# HabTrackerPiZero_Shield.net
KiCad netlist of a schematic drawn in EAGLE
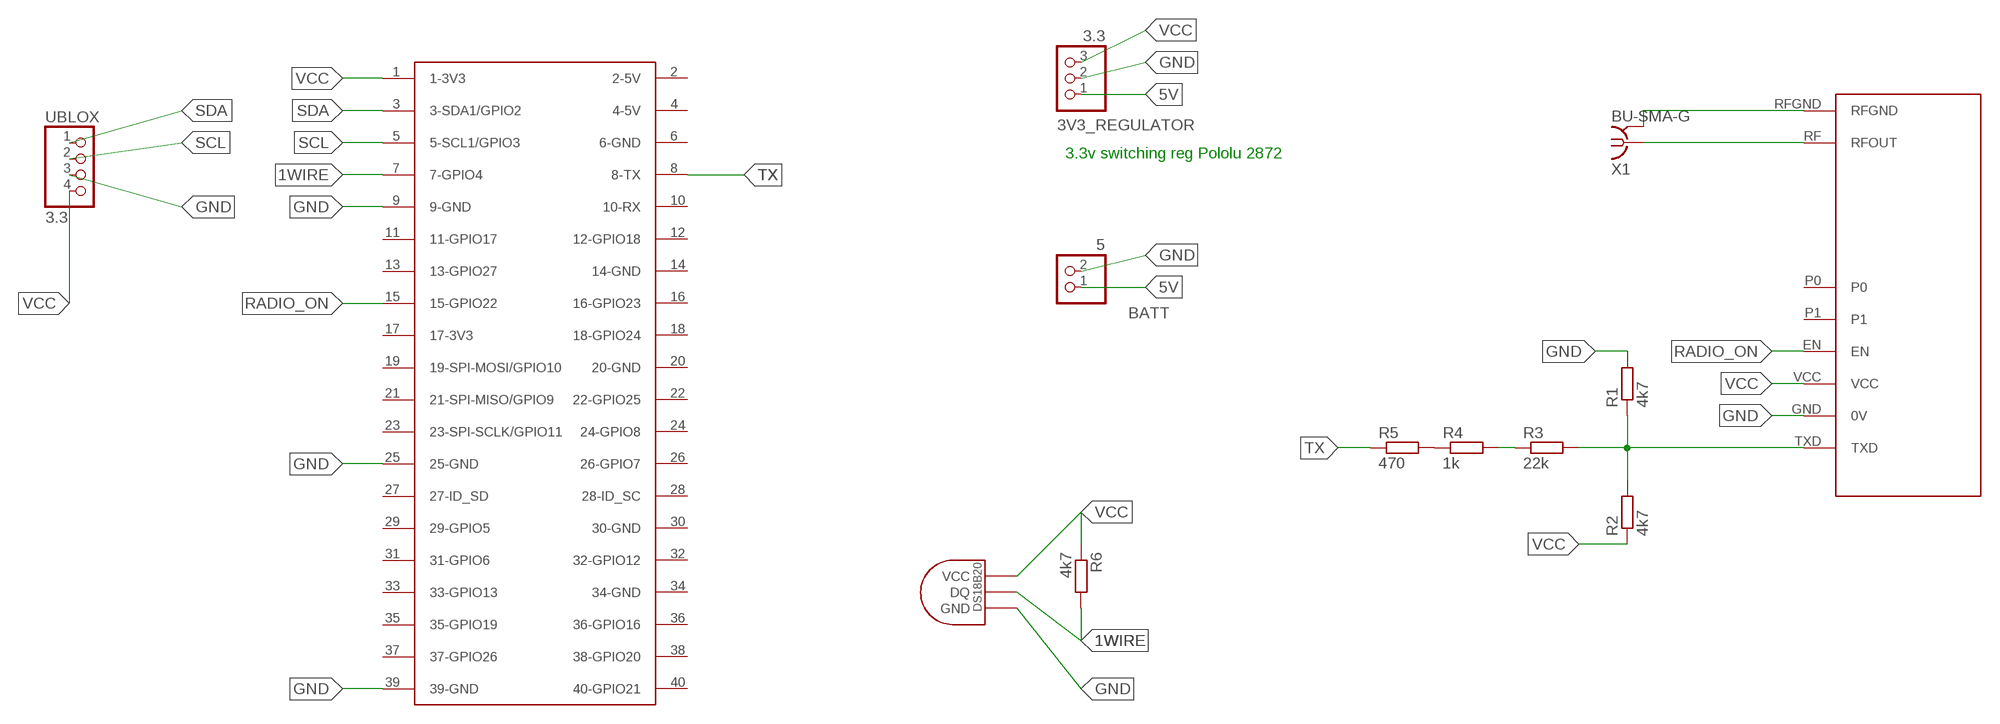
[diagram p0: schematic, sheet 1]

(export (version "E")
  (design (tool "Eeschema 10.0.6"))
  (components
    (comp (ref "3V3_REGULATOR")
      (value "3.3")
      (footprint "eagle-import:1X03")
      (libsource (lib "eagle-import") (part "PINHD-1X3"))
    )
    (comp (ref "BATT")
      (value "5")
      (footprint "eagle-import:1X02")
      (libsource (lib "eagle-import") (part "PINHD-1X2"))
    )
    (comp (ref "R1")
      (value "4k7")
      (footprint "eagle-import:0204_7")
      (libsource (lib "eagle-import") (part "R-EU_0204/7"))
    )
    (comp (ref "R2")
      (value "4k7")
      (footprint "eagle-import:0204_7")
      (libsource (lib "eagle-import") (part "R-EU_0204/7"))
    )
    (comp (ref "R3")
      (value "22k")
      (footprint "eagle-import:0204_7")
      (libsource (lib "eagle-import") (part "R-EU_0204/7"))
    )
    (comp (ref "R4")
      (value "1k")
      (footprint "eagle-import:0204_7")
      (libsource (lib "eagle-import") (part "R-EU_0204/7"))
    )
    (comp (ref "R5")
      (value "470")
      (footprint "eagle-import:0204_7")
      (libsource (lib "eagle-import") (part "R-EU_0204/7"))
    )
    (comp (ref "R6")
      (value "4k7")
      (footprint "eagle-import:0204_7")
      (libsource (lib "eagle-import") (part "R-EU_0204/7"))
    )
    (comp (ref "U$1")
      (value "RASPBERRY-PI+PIZERO")
      (footprint "eagle-import:RASPBERRY-PI-ZERO")
      (libsource (lib "eagle-import") (part "RASPBERRY-PI+PIZERO"))
    )
    (comp (ref "U$2")
      (value "DS1820TO92")
      (footprint "eagle-import:DS1820")
      (libsource (lib "eagle-import") (part "DS1820TO92"))
    )
    (comp (ref "U$3")
      (value "RADIOMETRIX-MTX2")
      (footprint "eagle-import:RADIOMETRIX-MTX2")
      (libsource (lib "eagle-import") (part "RADIOMETRIX-MTX2"))
    )
    (comp (ref "UBLOX")
      (value "3.3")
      (footprint "eagle-import:1X04")
      (libsource (lib "eagle-import") (part "PINHD-1X4"))
    )
    (comp (ref "X1")
      (value "BU-SMA-G")
      (footprint "eagle-import:BU-SMA-G")
      (libsource (lib "eagle-import") (part "BU-SMA-G"))
    )
  )
  (nets
    (net (code "1") (name "1WIRE") (class "Default")
      (node (ref "R6") (pin "2") (pinfunction "2_2") (pintype "passive"))
      (node (ref "U$1") (pin "7") (pinfunction "7-GPIO4_7") (pintype "bidirectional"))
      (node (ref "U$2") (pin "DQ") (pinfunction "DQ_DQ") (pintype "bidirectional"))
    )
    (net (code "2") (name "5V") (class "Default")
      (node (ref "3V3_REGULATOR") (pin "1") (pinfunction "1_1") (pintype "passive"))
      (node (ref "BATT") (pin "1") (pinfunction "1_1") (pintype "passive"))
    )
    (net (code "3") (name "GND") (class "Default")
      (node (ref "3V3_REGULATOR") (pin "2") (pinfunction "2_2") (pintype "passive"))
      (node (ref "BATT") (pin "2") (pinfunction "2_2") (pintype "passive"))
      (node (ref "R1") (pin "2") (pinfunction "2_2") (pintype "passive"))
      (node (ref "U$1") (pin "25") (pinfunction "25-GND_25") (pintype "bidirectional"))
      (node (ref "U$1") (pin "39") (pinfunction "39-GND_39") (pintype "bidirectional"))
      (node (ref "U$1") (pin "9") (pinfunction "9-GND_9") (pintype "bidirectional"))
      (node (ref "U$2") (pin "GND") (pinfunction "GND_GND") (pintype "power_in"))
      (node (ref "U$3") (pin "GND") (pinfunction "0V_GND") (pintype "bidirectional"))
      (node (ref "UBLOX") (pin "3") (pinfunction "3_3") (pintype "passive"))
    )
    (net (code "4") (name "Net-(R1-Pad1)") (class "Default")
      (node (ref "R1") (pin "1") (pinfunction "1_1") (pintype "passive"))
      (node (ref "R2") (pin "2") (pinfunction "2_2") (pintype "passive"))
      (node (ref "R3") (pin "2") (pinfunction "2_2") (pintype "passive"))
      (node (ref "U$3") (pin "TXD") (pinfunction "TXD_TXD") (pintype "bidirectional"))
    )
    (net (code "5") (name "Net-(R3-Pad1)") (class "Default")
      (node (ref "R3") (pin "1") (pinfunction "1_1") (pintype "passive"))
      (node (ref "R4") (pin "2") (pinfunction "2_2") (pintype "passive"))
    )
    (net (code "6") (name "Net-(R4-Pad1)") (class "Default")
      (node (ref "R4") (pin "1") (pinfunction "1_1") (pintype "passive"))
      (node (ref "R5") (pin "2") (pinfunction "2_2") (pintype "passive"))
    )
    (net (code "7") (name "Net-(U$3-PadRFGND)") (class "Default")
      (node (ref "U$3") (pin "RFGND") (pinfunction "RFGND_RFGND") (pintype "bidirectional"))
      (node (ref "X1") (pin "2") (pinfunction "2_2") (pintype "passive"))
      (node (ref "X1") (pin "3") (pinfunction "2_3") (pintype "passive"))
      (node (ref "X1") (pin "4") (pinfunction "2_4") (pintype "passive"))
      (node (ref "X1") (pin "5") (pinfunction "2_5") (pintype "passive"))
    )
    (net (code "8") (name "Net-(U$3-RFOUT)") (class "Default")
      (node (ref "U$3") (pin "RF") (pinfunction "RFOUT_RF") (pintype "bidirectional"))
      (node (ref "X1") (pin "1") (pinfunction "1_1") (pintype "passive"))
    )
    (net (code "9") (name "RADIO_ON") (class "Default")
      (node (ref "U$1") (pin "15") (pinfunction "15-GPIO22_15") (pintype "bidirectional"))
      (node (ref "U$3") (pin "EN") (pinfunction "EN_EN") (pintype "bidirectional"))
    )
    (net (code "10") (name "SCL") (class "Default")
      (node (ref "U$1") (pin "5") (pinfunction "5-SCL1/GPIO3_5") (pintype "bidirectional"))
      (node (ref "UBLOX") (pin "2") (pinfunction "2_2") (pintype "passive"))
    )
    (net (code "11") (name "SDA") (class "Default")
      (node (ref "U$1") (pin "3") (pinfunction "3-SDA1/GPIO2_3") (pintype "bidirectional"))
      (node (ref "UBLOX") (pin "1") (pinfunction "1_1") (pintype "passive"))
    )
    (net (code "12") (name "TX") (class "Default")
      (node (ref "R5") (pin "1") (pinfunction "1_1") (pintype "passive"))
      (node (ref "U$1") (pin "8") (pinfunction "8-TX_8") (pintype "bidirectional"))
    )
    (net (code "13") (name "VCC") (class "Default")
      (node (ref "3V3_REGULATOR") (pin "3") (pinfunction "3_3") (pintype "passive"))
      (node (ref "R2") (pin "1") (pinfunction "1_1") (pintype "passive"))
      (node (ref "R6") (pin "1") (pinfunction "1_1") (pintype "passive"))
      (node (ref "U$1") (pin "1") (pinfunction "1-3V3_1") (pintype "bidirectional"))
      (node (ref "U$2") (pin "VDD") (pinfunction "VCC_VDD") (pintype "power_in"))
      (node (ref "U$3") (pin "VCC") (pinfunction "VCC_VCC") (pintype "bidirectional"))
      (node (ref "UBLOX") (pin "4") (pinfunction "4_4") (pintype "passive"))
    )
    (net (code "14") (name "unconnected-(U$1-2-5V-Pad2)") (class "Default")
      (node (ref "U$1") (pin "2") (pinfunction "2-5V_2") (pintype "bidirectional"))
    )
    (net (code "15") (name "unconnected-(U$1-4-5V-Pad4)") (class "Default")
      (node (ref "U$1") (pin "4") (pinfunction "4-5V_4") (pintype "bidirectional"))
    )
    (net (code "16") (name "unconnected-(U$1-6-GND-Pad6)") (class "Default")
      (node (ref "U$1") (pin "6") (pinfunction "6-GND_6") (pintype "bidirectional"))
    )
    (net (code "17") (name "unconnected-(U$1-10-RX-Pad10)") (class "Default")
      (node (ref "U$1") (pin "10") (pinfunction "10-RX_10") (pintype "bidirectional"))
    )
    (net (code "18") (name "unconnected-(U$1-11-GPIO17-Pad11)") (class "Default")
      (node (ref "U$1") (pin "11") (pinfunction "11-GPIO17_11") (pintype "bidirectional"))
    )
    (net (code "19") (name "unconnected-(U$1-12-GPIO18-Pad12)") (class "Default")
      (node (ref "U$1") (pin "12") (pinfunction "12-GPIO18_12") (pintype "bidirectional"))
    )
    (net (code "20") (name "unconnected-(U$1-13-GPIO27-Pad13)") (class "Default")
      (node (ref "U$1") (pin "13") (pinfunction "13-GPIO27_13") (pintype "bidirectional"))
    )
    (net (code "21") (name "unconnected-(U$1-14-GND-Pad14)") (class "Default")
      (node (ref "U$1") (pin "14") (pinfunction "14-GND_14") (pintype "bidirectional"))
    )
    (net (code "22") (name "unconnected-(U$1-16-GPIO23-Pad16)") (class "Default")
      (node (ref "U$1") (pin "16") (pinfunction "16-GPIO23_16") (pintype "bidirectional"))
    )
    (net (code "23") (name "unconnected-(U$1-17-3V3-Pad17)") (class "Default")
      (node (ref "U$1") (pin "17") (pinfunction "17-3V3_17") (pintype "bidirectional"))
    )
    (net (code "24") (name "unconnected-(U$1-18-GPIO24-Pad18)") (class "Default")
      (node (ref "U$1") (pin "18") (pinfunction "18-GPIO24_18") (pintype "bidirectional"))
    )
    (net (code "25") (name "unconnected-(U$1-19-SPI-MOSI{slash}GPIO10-Pad19)") (class "Default")
      (node (ref "U$1") (pin "19") (pinfunction "19-SPI-MOSI/GPIO10_19") (pintype "bidirectional"))
    )
    (net (code "26") (name "unconnected-(U$1-20-GND-Pad20)") (class "Default")
      (node (ref "U$1") (pin "20") (pinfunction "20-GND_20") (pintype "bidirectional"))
    )
    (net (code "27") (name "unconnected-(U$1-21-SPI-MISO{slash}GPIO9-Pad21)") (class "Default")
      (node (ref "U$1") (pin "21") (pinfunction "21-SPI-MISO/GPIO9_21") (pintype "bidirectional"))
    )
    (net (code "28") (name "unconnected-(U$1-22-GPIO25-Pad22)") (class "Default")
      (node (ref "U$1") (pin "22") (pinfunction "22-GPIO25_22") (pintype "bidirectional"))
    )
    (net (code "29") (name "unconnected-(U$1-23-SPI-SCLK{slash}GPIO11-Pad23)") (class "Default")
      (node (ref "U$1") (pin "23") (pinfunction "23-SPI-SCLK/GPIO11_23") (pintype "bidirectional"))
    )
    (net (code "30") (name "unconnected-(U$1-24-GPIO8-Pad24)") (class "Default")
      (node (ref "U$1") (pin "24") (pinfunction "24-GPIO8_24") (pintype "bidirectional"))
    )
    (net (code "31") (name "unconnected-(U$1-26-GPIO7-Pad26)") (class "Default")
      (node (ref "U$1") (pin "26") (pinfunction "26-GPIO7_26") (pintype "bidirectional"))
    )
    (net (code "32") (name "unconnected-(U$1-27-ID_SD-Pad27)") (class "Default")
      (node (ref "U$1") (pin "27") (pinfunction "27-ID_SD_27") (pintype "bidirectional"))
    )
    (net (code "33") (name "unconnected-(U$1-28-ID_SC-Pad28)") (class "Default")
      (node (ref "U$1") (pin "28") (pinfunction "28-ID_SC_28") (pintype "bidirectional"))
    )
    (net (code "34") (name "unconnected-(U$1-29-GPIO5-Pad29)") (class "Default")
      (node (ref "U$1") (pin "29") (pinfunction "29-GPIO5_29") (pintype "bidirectional"))
    )
    (net (code "35") (name "unconnected-(U$1-30-GND-Pad30)") (class "Default")
      (node (ref "U$1") (pin "30") (pinfunction "30-GND_30") (pintype "bidirectional"))
    )
    (net (code "36") (name "unconnected-(U$1-31-GPIO6-Pad31)") (class "Default")
      (node (ref "U$1") (pin "31") (pinfunction "31-GPIO6_31") (pintype "bidirectional"))
    )
    (net (code "37") (name "unconnected-(U$1-32-GPIO12-Pad32)") (class "Default")
      (node (ref "U$1") (pin "32") (pinfunction "32-GPIO12_32") (pintype "bidirectional"))
    )
    (net (code "38") (name "unconnected-(U$1-33-GPIO13-Pad33)") (class "Default")
      (node (ref "U$1") (pin "33") (pinfunction "33-GPIO13_33") (pintype "bidirectional"))
    )
    (net (code "39") (name "unconnected-(U$1-34-GND-Pad34)") (class "Default")
      (node (ref "U$1") (pin "34") (pinfunction "34-GND_34") (pintype "bidirectional"))
    )
    (net (code "40") (name "unconnected-(U$1-35-GPIO19-Pad35)") (class "Default")
      (node (ref "U$1") (pin "35") (pinfunction "35-GPIO19_35") (pintype "bidirectional"))
    )
    (net (code "41") (name "unconnected-(U$1-36-GPIO16-Pad36)") (class "Default")
      (node (ref "U$1") (pin "36") (pinfunction "36-GPIO16_36") (pintype "bidirectional"))
    )
    (net (code "42") (name "unconnected-(U$1-37-GPIO26-Pad37)") (class "Default")
      (node (ref "U$1") (pin "37") (pinfunction "37-GPIO26_37") (pintype "bidirectional"))
    )
    (net (code "43") (name "unconnected-(U$1-38-GPIO20-Pad38)") (class "Default")
      (node (ref "U$1") (pin "38") (pinfunction "38-GPIO20_38") (pintype "bidirectional"))
    )
    (net (code "44") (name "unconnected-(U$1-40-GPIO21-Pad40)") (class "Default")
      (node (ref "U$1") (pin "40") (pinfunction "40-GPIO21_40") (pintype "bidirectional"))
    )
    (net (code "45") (name "unconnected-(U$3-PadP0)") (class "Default")
      (node (ref "U$3") (pin "P0") (pinfunction "P0_P0") (pintype "bidirectional"))
    )
    (net (code "46") (name "unconnected-(U$3-PadP1)") (class "Default")
      (node (ref "U$3") (pin "P1") (pinfunction "P1_P1") (pintype "bidirectional"))
    )
  )
)
